# Motor_Driver.net
KiCad netlist of a schematic drawn in Altium Designer
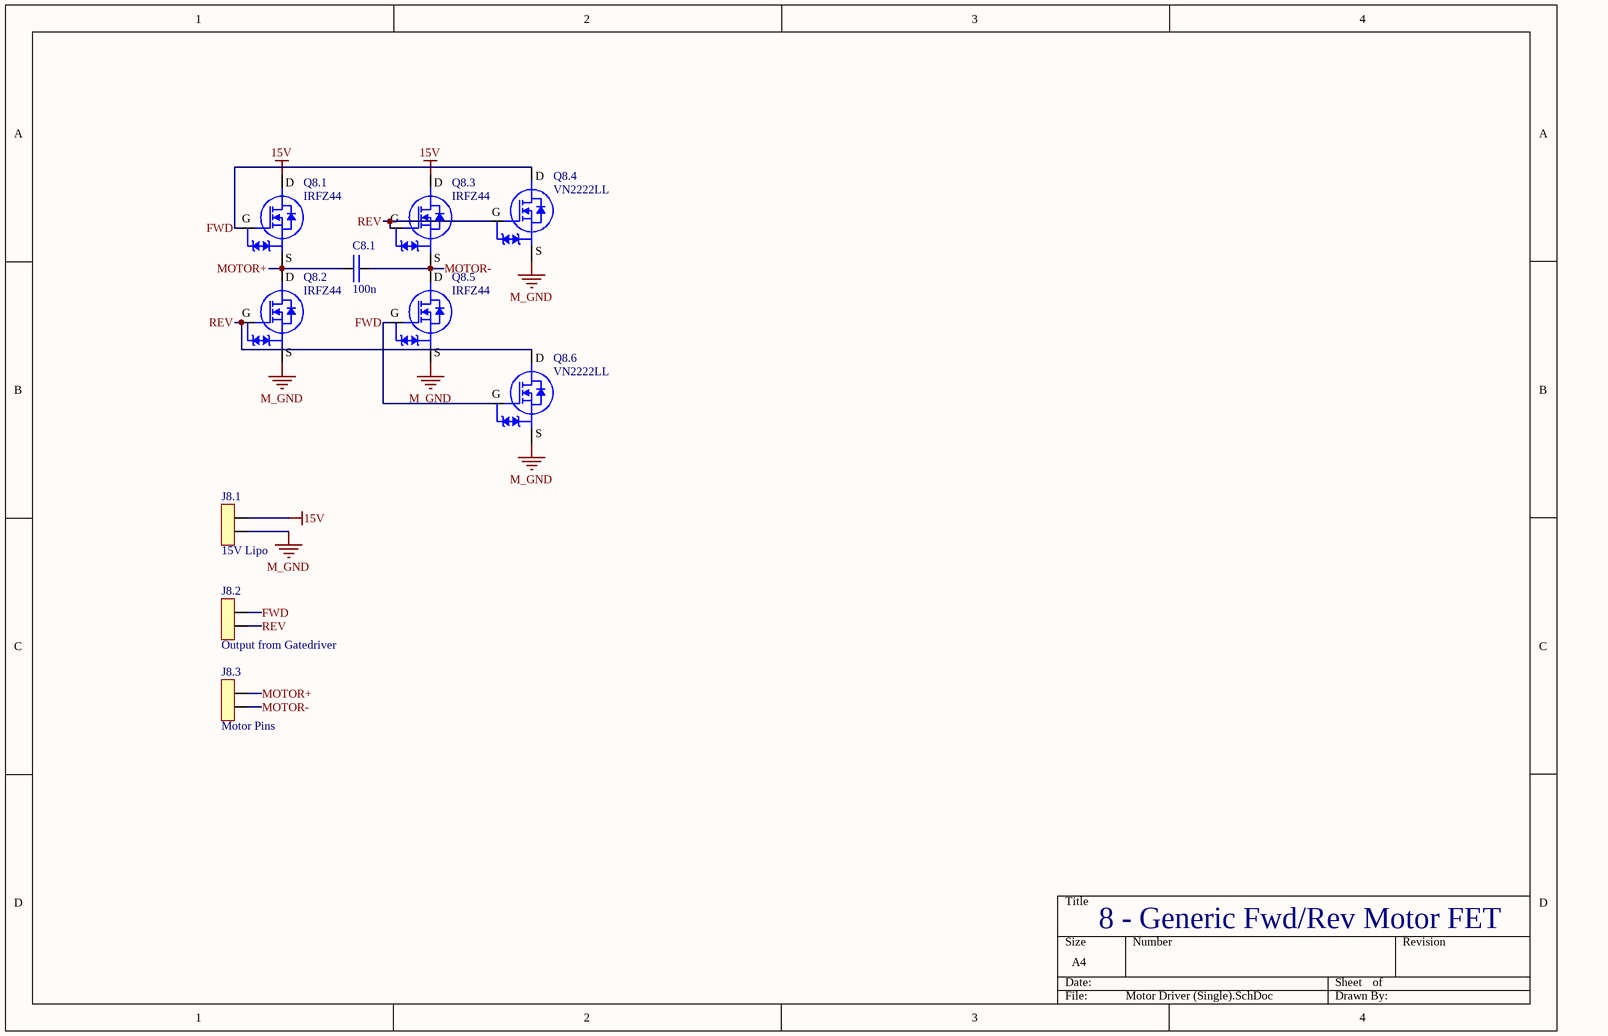
[diagram p0: Motor Driver (Single).SchDoc]

(export (version "E")
  (design (tool "Eeschema 10.0.6"))
  (components
    (comp (ref "C8.1")
      (value "100n")
      (footprint "Non Polarized Cap")
      (libsource (lib "SPICEBot_SchLib") (part "Cap_Generic"))
    )
    (comp (ref "J8.1")
      (value "15V Lipo")
      (footprint "2pos JST")
      (description "2pos Conn JST")
      (libsource (lib "SPICEBot_SchLib") (part "2pos Conn"))
    )
    (comp (ref "J8.2")
      (value "Output from Gatedriver")
      (footprint "2pos JST")
      (libsource (lib "SPICEBot_SchLib") (part "2pos Conn"))
    )
    (comp (ref "J8.3")
      (value "Motor Pins")
      (footprint "2pos JST")
      (libsource (lib "SPICEBot_SchLib") (part "2pos Conn"))
    )
    (comp (ref "Q8.1")
      (value "IRFZ44")
      (footprint "TO220")
      (description "IRFZ44EPBF N-Channel 60 V 48A 110W Through Hole TO-220AB")
      (libsource (lib "SPICEBot_SchLib") (part "IRFZ44 NMOS"))
    )
    (comp (ref "Q8.2")
      (value "IRFZ44")
      (footprint "TO220")
      (description "IRFZ44EPBF N-Channel 60 V 48A 110W Through Hole TO-220AB")
      (libsource (lib "SPICEBot_SchLib") (part "IRFZ44 NMOS"))
    )
    (comp (ref "Q8.3")
      (value "IRFZ44")
      (footprint "TO220")
      (description "IRFZ44EPBF N-Channel 60 V 48A 110W Through Hole TO-220AB")
      (libsource (lib "SPICEBot_SchLib") (part "IRFZ44 NMOS"))
    )
    (comp (ref "Q8.4")
      (value "VN2222LL")
      (footprint "VN2222LL")
      (description "VN2222LL N-Channel 60 V 150mA 400mW Through Hole TO-92 (TO-226)")
      (libsource (lib "SPICEBot_SchLib") (part "VN2222LL NMOS"))
    )
    (comp (ref "Q8.5")
      (value "IRFZ44")
      (footprint "TO220")
      (description "IRFZ44EPBF N-Channel 60 V 48A 110W Through Hole TO-220AB")
      (libsource (lib "SPICEBot_SchLib") (part "IRFZ44 NMOS"))
    )
    (comp (ref "Q8.6")
      (value "VN2222LL")
      (footprint "VN2222LL")
      (description "VN2222LL N-Channel 60 V 150mA 400mW Through Hole TO-92 (TO-226)")
      (libsource (lib "SPICEBot_SchLib") (part "VN2222LL NMOS"))
    )
  )
  (nets
    (net (code "1") (name "/FWD") (class "Default")
      (node (ref "J8.2") (pin "2") (pinfunction "2_2") (pintype "passive"))
      (node (ref "Q8.1") (pin "1") (pinfunction "G_1") (pintype "passive"))
      (node (ref "Q8.4") (pin "3") (pinfunction "D_3") (pintype "passive"))
      (node (ref "Q8.5") (pin "1") (pinfunction "G_1") (pintype "passive"))
      (node (ref "Q8.6") (pin "2") (pinfunction "G_2") (pintype "passive"))
    )
    (net (code "2") (name "/MOTOR+") (class "Default")
      (node (ref "C8.1") (pin "1") (pinfunction "1_1") (pintype "passive"))
      (node (ref "J8.3") (pin "2") (pinfunction "2_2") (pintype "passive"))
      (node (ref "Q8.1") (pin "3") (pinfunction "S_3") (pintype "passive"))
      (node (ref "Q8.2") (pin "2") (pinfunction "D_2") (pintype "passive"))
    )
    (net (code "3") (name "/MOTOR-") (class "Default")
      (node (ref "C8.1") (pin "2") (pinfunction "2_2") (pintype "passive"))
      (node (ref "J8.3") (pin "1") (pinfunction "1_1") (pintype "passive"))
      (node (ref "Q8.3") (pin "3") (pinfunction "S_3") (pintype "passive"))
      (node (ref "Q8.5") (pin "2") (pinfunction "D_2") (pintype "passive"))
    )
    (net (code "4") (name "/REV") (class "Default")
      (node (ref "J8.2") (pin "1") (pinfunction "1_1") (pintype "passive"))
      (node (ref "Q8.2") (pin "1") (pinfunction "G_1") (pintype "passive"))
      (node (ref "Q8.3") (pin "1") (pinfunction "G_1") (pintype "passive"))
      (node (ref "Q8.4") (pin "2") (pinfunction "G_2") (pintype "passive"))
      (node (ref "Q8.6") (pin "3") (pinfunction "D_3") (pintype "passive"))
    )
    (net (code "5") (name "15V") (class "Default")
      (node (ref "J8.1") (pin "2") (pinfunction "2_2") (pintype "passive"))
      (node (ref "Q8.1") (pin "2") (pinfunction "D_2") (pintype "passive"))
      (node (ref "Q8.3") (pin "2") (pinfunction "D_2") (pintype "passive"))
    )
    (net (code "6") (name "M_GND") (class "Default")
      (node (ref "J8.1") (pin "1") (pinfunction "1_1") (pintype "passive"))
      (node (ref "Q8.2") (pin "3") (pinfunction "S_3") (pintype "passive"))
      (node (ref "Q8.4") (pin "1") (pinfunction "S_1") (pintype "passive"))
      (node (ref "Q8.5") (pin "3") (pinfunction "S_3") (pintype "passive"))
      (node (ref "Q8.6") (pin "1") (pinfunction "S_1") (pintype "passive"))
    )
  )
)
